# Current_Sensor.net
KiCad netlist of a schematic drawn in Altium Designer
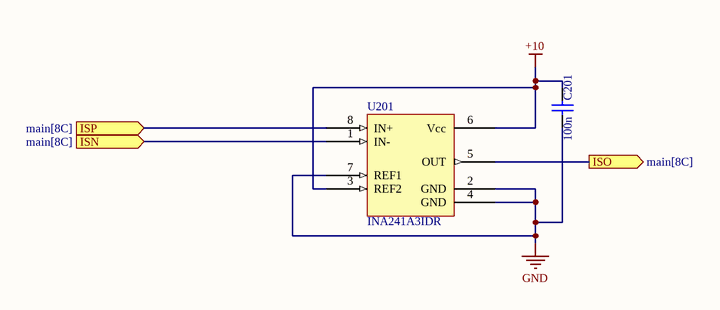
[diagram p0: Current_Sensor.SchDoc]

(export (version "E")
  (design (tool "Eeschema 10.0.6"))
  (components
    (comp (ref "C201")
      (value "100n")
      (footprint "CAP_1206")
      (description "Non Polarized Capacitor, SMD, 1206")
      (libsource (lib "Resistors and Capacitors") (part "CAPN 1206"))
    )
    (comp (ref "U201")
      (value "INA241A3IDR")
      (footprint "SOIC8_M")
      (description "Current Sense Amp")
      (libsource (lib "Projects_2025") (part "INA241A3IDR"))
    )
  )
  (nets
    (net (code "1") (name "+10") (class "Default")
      (node (ref "C201") (pin "2") (pinfunction "2_2") (pintype "passive"))
      (node (ref "U201") (pin "3") (pinfunction "REF2_3") (pintype "input"))
      (node (ref "U201") (pin "6") (pinfunction "Vcc_6") (pintype "power_in"))
    )
    (net (code "2") (name "/ISN") (class "Default")
      (node (ref "U201") (pin "1") (pinfunction "IN-_1") (pintype "input"))
    )
    (net (code "3") (name "/ISO") (class "Default")
      (node (ref "U201") (pin "5") (pinfunction "OUT_5") (pintype "output"))
    )
    (net (code "4") (name "/ISP") (class "Default")
      (node (ref "U201") (pin "8") (pinfunction "IN+_8") (pintype "input"))
    )
    (net (code "5") (name "GND") (class "Default")
      (node (ref "C201") (pin "1") (pinfunction "1_1") (pintype "passive"))
      (node (ref "U201") (pin "2") (pinfunction "GND_2") (pintype "power_in"))
      (node (ref "U201") (pin "4") (pinfunction "GND_4") (pintype "passive"))
      (node (ref "U201") (pin "7") (pinfunction "REF1_7") (pintype "input"))
    )
  )
)
